# Flexbus_Cable.net
KiCad netlist of a schematic drawn in EasyEDA Pro
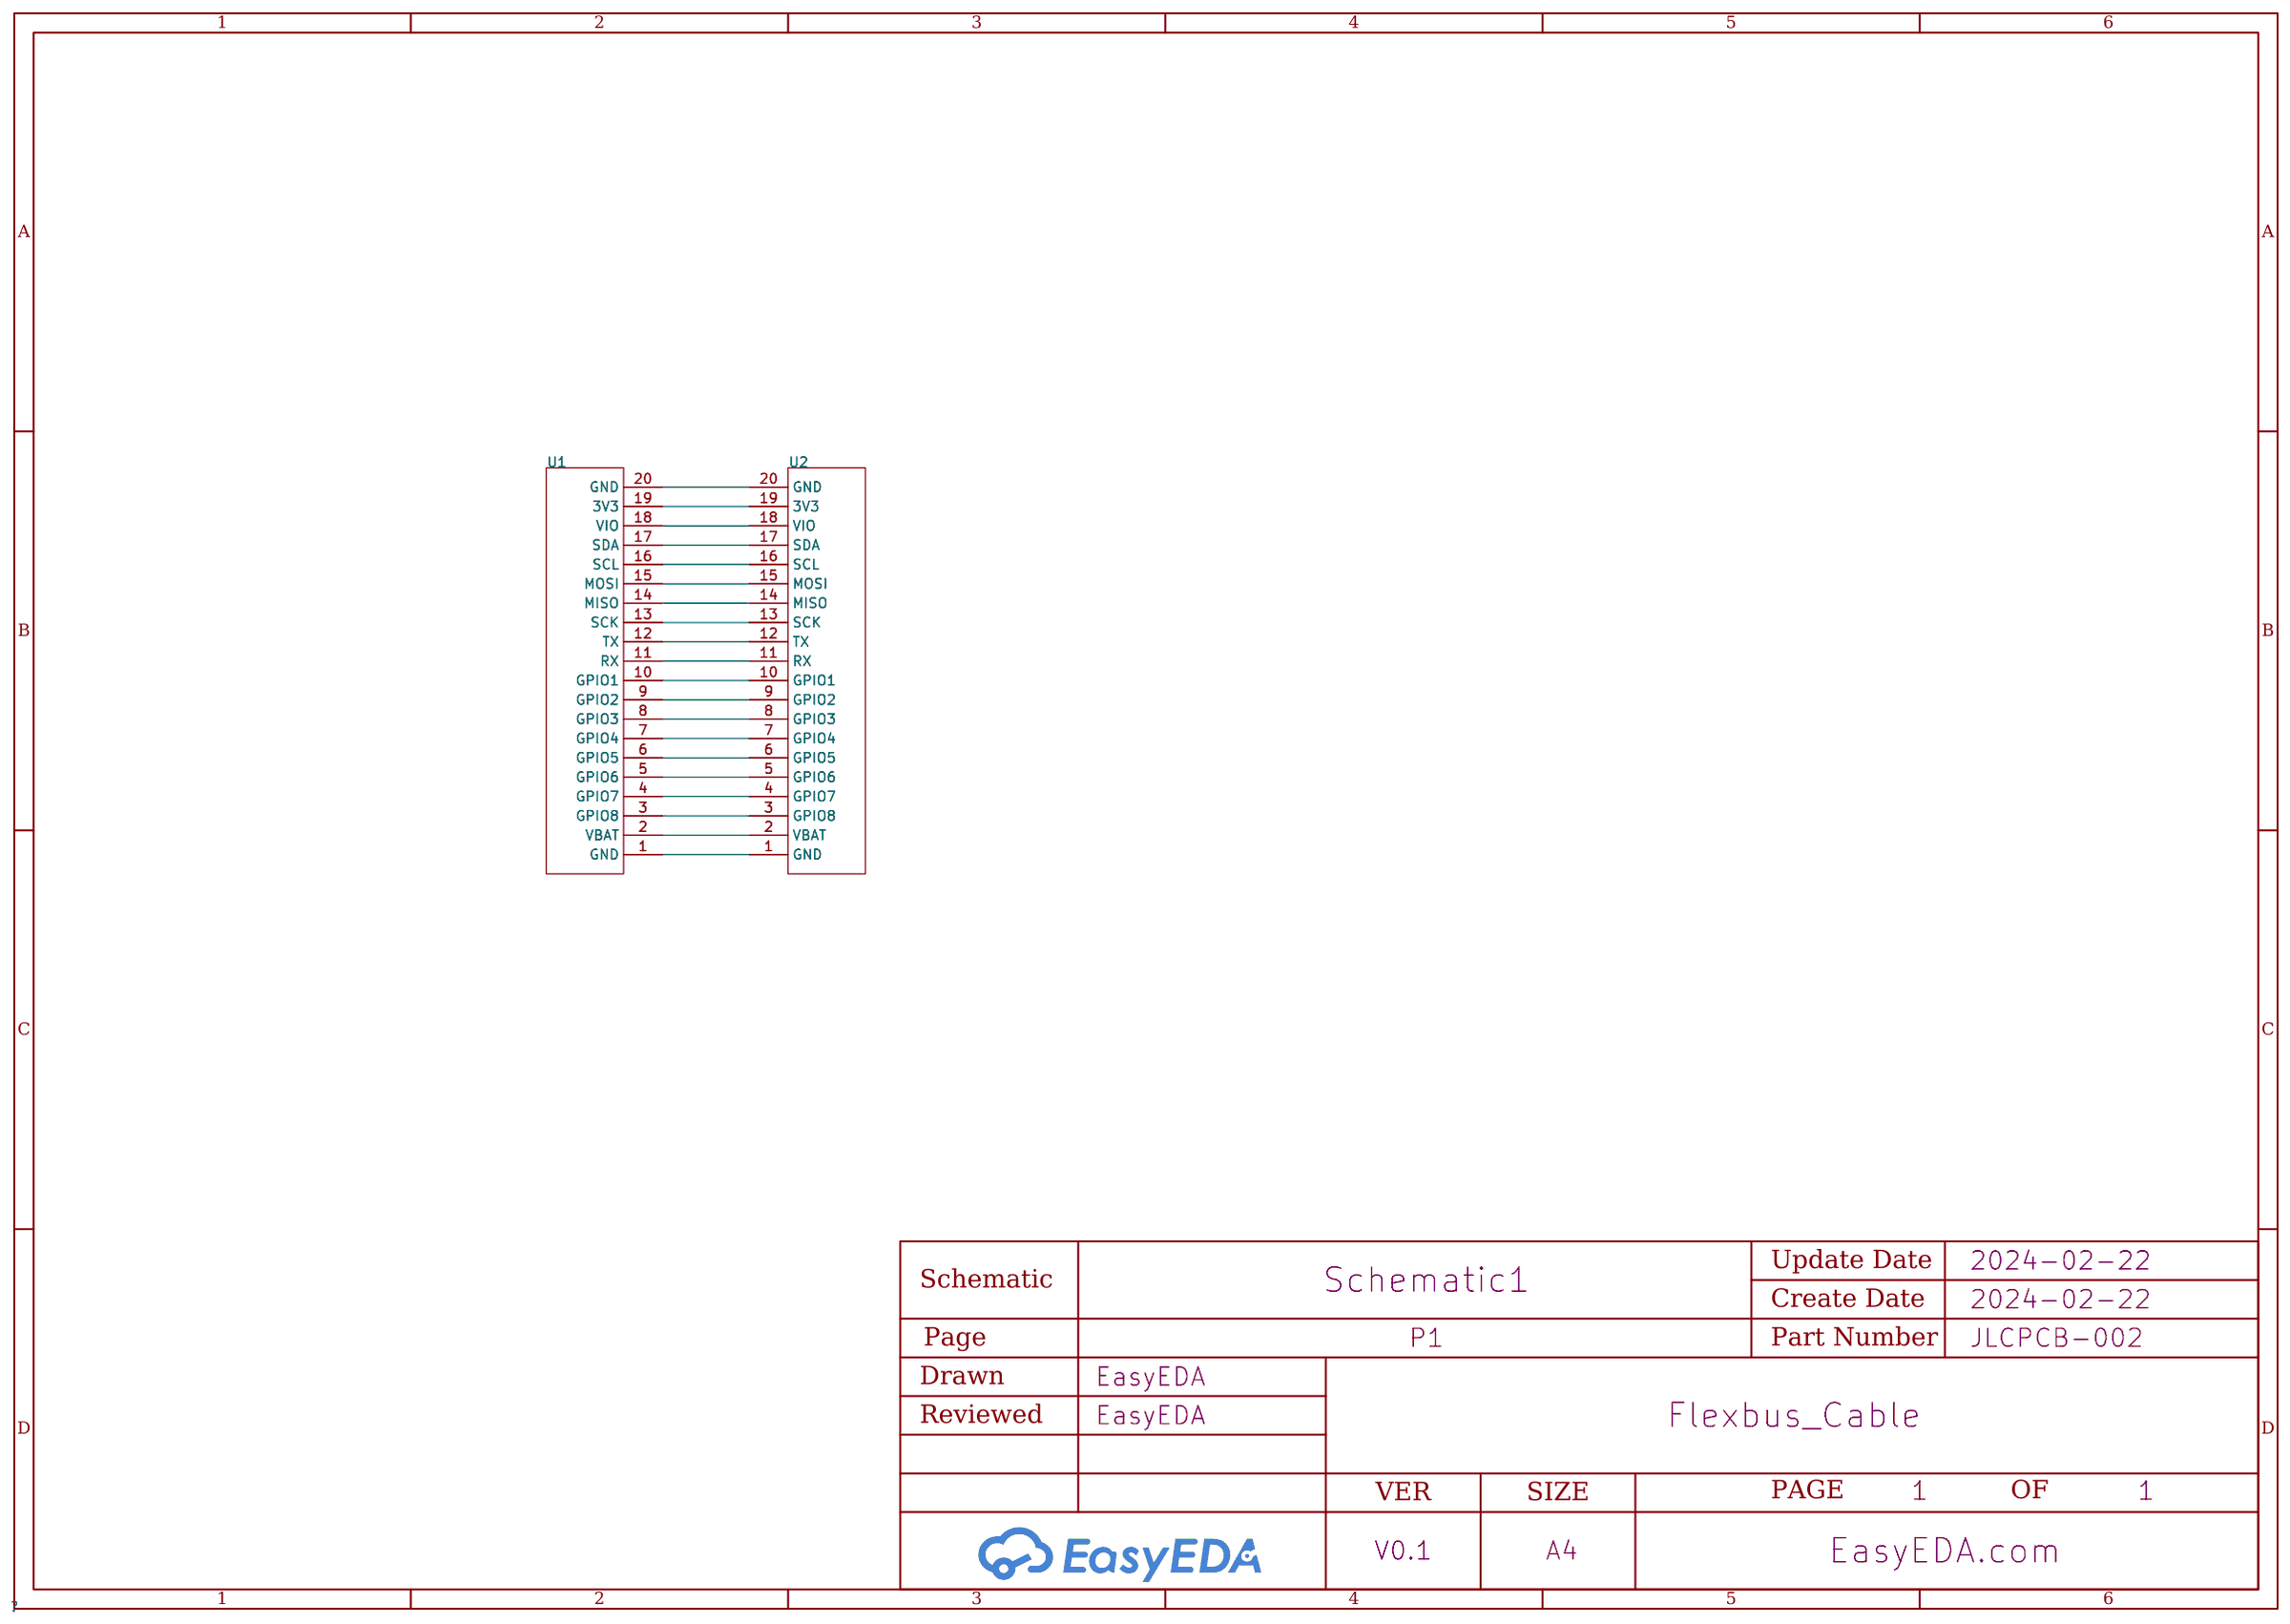
[diagram p0: schematic sheet]

(export (version "E")
  (design (tool "Eeschema 10.0.6"))
  (components
    (comp (ref "U1")
      (value "~")
      (footprint "easyedapro:FPC 0.5mm 20P")
      (libsource (lib "easyedapro") (part "FlexBus FPC 0.5mm 20P"))
    )
    (comp (ref "U2")
      (value "~")
      (footprint "easyedapro:FPC 0.5mm 20P")
      (libsource (lib "easyedapro") (part "FlexBus FPC 0.5mm 20P"))
    )
  )
  (nets
    (net (code "1") (name "Net-(U1-3V3)") (class "Default")
      (node (ref "U1") (pin "19") (pinfunction "3V3_19") (pintype "input"))
      (node (ref "U2") (pin "19") (pinfunction "3V3_19") (pintype "input"))
    )
    (net (code "2") (name "Net-(U1-GND-Pad1)") (class "Default")
      (node (ref "U1") (pin "1") (pinfunction "GND_1") (pintype "input"))
      (node (ref "U2") (pin "1") (pinfunction "GND_1") (pintype "input"))
    )
    (net (code "3") (name "Net-(U1-GND-Pad20)") (class "Default")
      (node (ref "U1") (pin "20") (pinfunction "GND_20") (pintype "input"))
      (node (ref "U2") (pin "20") (pinfunction "GND_20") (pintype "input"))
    )
    (net (code "4") (name "Net-(U1-GPIO1)") (class "Default")
      (node (ref "U1") (pin "10") (pinfunction "GPIO1_10") (pintype "input"))
      (node (ref "U2") (pin "10") (pinfunction "GPIO1_10") (pintype "input"))
    )
    (net (code "5") (name "Net-(U1-GPIO2)") (class "Default")
      (node (ref "U1") (pin "9") (pinfunction "GPIO2_9") (pintype "input"))
      (node (ref "U2") (pin "9") (pinfunction "GPIO2_9") (pintype "input"))
    )
    (net (code "6") (name "Net-(U1-GPIO3)") (class "Default")
      (node (ref "U1") (pin "8") (pinfunction "GPIO3_8") (pintype "input"))
      (node (ref "U2") (pin "8") (pinfunction "GPIO3_8") (pintype "input"))
    )
    (net (code "7") (name "Net-(U1-GPIO4)") (class "Default")
      (node (ref "U1") (pin "7") (pinfunction "GPIO4_7") (pintype "input"))
      (node (ref "U2") (pin "7") (pinfunction "GPIO4_7") (pintype "input"))
    )
    (net (code "8") (name "Net-(U1-GPIO5)") (class "Default")
      (node (ref "U1") (pin "6") (pinfunction "GPIO5_6") (pintype "input"))
      (node (ref "U2") (pin "6") (pinfunction "GPIO5_6") (pintype "input"))
    )
    (net (code "9") (name "Net-(U1-GPIO6)") (class "Default")
      (node (ref "U1") (pin "5") (pinfunction "GPIO6_5") (pintype "input"))
      (node (ref "U2") (pin "5") (pinfunction "GPIO6_5") (pintype "input"))
    )
    (net (code "10") (name "Net-(U1-GPIO7)") (class "Default")
      (node (ref "U1") (pin "4") (pinfunction "GPIO7_4") (pintype "input"))
      (node (ref "U2") (pin "4") (pinfunction "GPIO7_4") (pintype "input"))
    )
    (net (code "11") (name "Net-(U1-GPIO8)") (class "Default")
      (node (ref "U1") (pin "3") (pinfunction "GPIO8_3") (pintype "input"))
      (node (ref "U2") (pin "3") (pinfunction "GPIO8_3") (pintype "input"))
    )
    (net (code "12") (name "Net-(U1-MISO)") (class "Default")
      (node (ref "U1") (pin "14") (pinfunction "MISO_14") (pintype "input"))
      (node (ref "U2") (pin "14") (pinfunction "MISO_14") (pintype "input"))
    )
    (net (code "13") (name "Net-(U1-MOSI)") (class "Default")
      (node (ref "U1") (pin "15") (pinfunction "MOSI_15") (pintype "input"))
      (node (ref "U2") (pin "15") (pinfunction "MOSI_15") (pintype "input"))
    )
    (net (code "14") (name "Net-(U1-RX)") (class "Default")
      (node (ref "U1") (pin "11") (pinfunction "RX_11") (pintype "input"))
      (node (ref "U2") (pin "11") (pinfunction "RX_11") (pintype "input"))
    )
    (net (code "15") (name "Net-(U1-SCK)") (class "Default")
      (node (ref "U1") (pin "13") (pinfunction "SCK_13") (pintype "input"))
      (node (ref "U2") (pin "13") (pinfunction "SCK_13") (pintype "input"))
    )
    (net (code "16") (name "Net-(U1-SCL)") (class "Default")
      (node (ref "U1") (pin "16") (pinfunction "SCL_16") (pintype "input"))
      (node (ref "U2") (pin "16") (pinfunction "SCL_16") (pintype "input"))
    )
    (net (code "17") (name "Net-(U1-SDA)") (class "Default")
      (node (ref "U1") (pin "17") (pinfunction "SDA_17") (pintype "input"))
      (node (ref "U2") (pin "17") (pinfunction "SDA_17") (pintype "input"))
    )
    (net (code "18") (name "Net-(U1-TX)") (class "Default")
      (node (ref "U1") (pin "12") (pinfunction "TX_12") (pintype "input"))
      (node (ref "U2") (pin "12") (pinfunction "TX_12") (pintype "input"))
    )
    (net (code "19") (name "Net-(U1-VBAT)") (class "Default")
      (node (ref "U1") (pin "2") (pinfunction "VBAT_2") (pintype "input"))
      (node (ref "U2") (pin "2") (pinfunction "VBAT_2") (pintype "input"))
    )
    (net (code "20") (name "Net-(U1-VIO)") (class "Default")
      (node (ref "U1") (pin "18") (pinfunction "VIO_18") (pintype "input"))
      (node (ref "U2") (pin "18") (pinfunction "VIO_18") (pintype "input"))
    )
  )
)
